# MCISO-S08-V00-HallDifferentials.net
KiCad netlist of a schematic drawn in Altium Designer
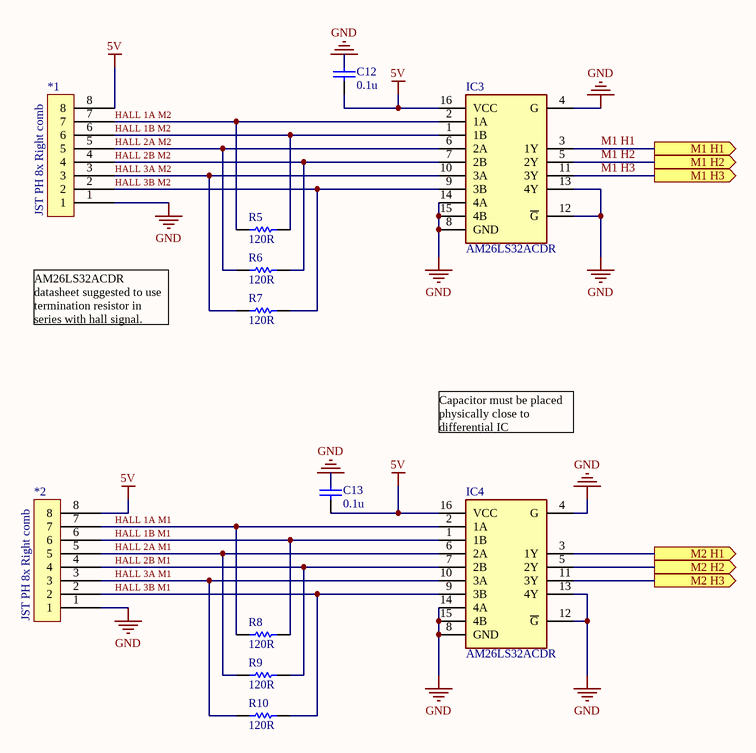
[diagram p0: MCISO-S08-V00-HallDifferentials.SchDoc]

(export (version "E")
  (design (tool "Eeschema 10.0.6"))
  (components
    (comp (ref "*1")
      (value "JST PH 8x Right comb")
      (footprint "JST PH 8x RIGHT SMD")
      (libsource (lib "QUTMS-MCISOLibrary") (part "JST PH 8x Right comb"))
    )
    (comp (ref "*2")
      (value "JST PH 8x Right comb")
      (footprint "JST PH 8x RIGHT SMD")
      (libsource (lib "QUTMS-MCISOLibrary") (part "JST PH 8x Right comb"))
    )
    (comp (ref "C12")
      (value "0.1u")
      (footprint "Cap_Ceramic_0603")
      (description "Capacitor, Ceramic, SMD, 4u7, 50V, 5%, X7R, 0603")
      (libsource (lib "QUTMS-MCISOLibrary") (part "4u7 50V 5% X7R 0603"))
    )
    (comp (ref "C13")
      (value "0.1u")
      (footprint "Cap_Ceramic_0603")
      (description "Capacitor, Ceramic, SMD, 4u7, 50V, 5%, X7R, 0603")
      (libsource (lib "QUTMS-MCISOLibrary") (part "4u7 50V 5% X7R 0603"))
    )
    (comp (ref "IC3")
      (value "AM26LS32ACDR")
      (footprint "SamacSys:SOIC127P600X175-16N")
      (description "Integrated Circuit")
      (fields (field (name "MOUSER PART NUMBER") "595-AM26LS32ACDR"))
      (libsource (lib "QUTMS-MCISOLibrary") (part "AM26LS32ACDR"))
    )
    (comp (ref "IC4")
      (value "AM26LS32ACDR")
      (footprint "SamacSys:SOIC127P600X175-16N")
      (description "Integrated Circuit")
      (fields (field (name "MOUSER PART NUMBER") "595-AM26LS32ACDR"))
      (libsource (lib "QUTMS-MCISOLibrary") (part "AM26LS32ACDR"))
    )
    (comp (ref "R5")
      (value "120R")
      (footprint "Res_ThinFilm_1210")
      (description "Resistor, SMD, 120R, 0.25W, 1%, 1210")
      (libsource (lib "QUTMS-MCISOLibrary") (part "120R 1% 1210"))
    )
    (comp (ref "R6")
      (value "120R")
      (footprint "Res_ThinFilm_1210")
      (description "Resistor, SMD, 120R, 0.25W, 1%, 1210")
      (libsource (lib "QUTMS-MCISOLibrary") (part "120R 1% 1210"))
    )
    (comp (ref "R7")
      (value "120R")
      (footprint "Res_ThinFilm_1210")
      (description "Resistor, SMD, 120R, 0.25W, 1%, 1210")
      (libsource (lib "QUTMS-MCISOLibrary") (part "120R 1% 1210"))
    )
    (comp (ref "R8")
      (value "120R")
      (footprint "Res_ThinFilm_1210")
      (description "Resistor, SMD, 120R, 0.25W, 1%, 1210")
      (libsource (lib "QUTMS-MCISOLibrary") (part "120R 1% 1210"))
    )
    (comp (ref "R9")
      (value "120R")
      (footprint "Res_ThinFilm_1210")
      (description "Resistor, SMD, 120R, 0.25W, 1%, 1210")
      (libsource (lib "QUTMS-MCISOLibrary") (part "120R 1% 1210"))
    )
    (comp (ref "R10")
      (value "120R")
      (footprint "Res_ThinFilm_1210")
      (description "Resistor, SMD, 120R, 0.25W, 1%, 1210")
      (libsource (lib "QUTMS-MCISOLibrary") (part "120R 1% 1210"))
    )
  )
  (nets
    (net (code "1") (name "/HALL 1A M1") (class "Default")
      (node (ref "*2") (pin "7") (pinfunction "7_7") (pintype "passive"))
      (node (ref "IC4") (pin "2") (pinfunction "1A_2") (pintype "passive"))
      (node (ref "R8") (pin "1") (pinfunction "1_1") (pintype "passive"))
    )
    (net (code "2") (name "/HALL 1A M2") (class "Default")
      (node (ref "*1") (pin "7") (pinfunction "7_7") (pintype "passive"))
      (node (ref "IC3") (pin "2") (pinfunction "1A_2") (pintype "passive"))
      (node (ref "R5") (pin "1") (pinfunction "1_1") (pintype "passive"))
    )
    (net (code "3") (name "/HALL 1B M1") (class "Default")
      (node (ref "*2") (pin "6") (pinfunction "6_6") (pintype "passive"))
      (node (ref "IC4") (pin "1") (pinfunction "1B_1") (pintype "passive"))
      (node (ref "R8") (pin "2") (pinfunction "2_2") (pintype "passive"))
    )
    (net (code "4") (name "/HALL 1B M2") (class "Default")
      (node (ref "*1") (pin "6") (pinfunction "6_6") (pintype "passive"))
      (node (ref "IC3") (pin "1") (pinfunction "1B_1") (pintype "passive"))
      (node (ref "R5") (pin "2") (pinfunction "2_2") (pintype "passive"))
    )
    (net (code "5") (name "/HALL 2A M1") (class "Default")
      (node (ref "*2") (pin "5") (pinfunction "5_5") (pintype "passive"))
      (node (ref "IC4") (pin "6") (pinfunction "2A_6") (pintype "passive"))
      (node (ref "R9") (pin "1") (pinfunction "1_1") (pintype "passive"))
    )
    (net (code "6") (name "/HALL 2A M2") (class "Default")
      (node (ref "*1") (pin "5") (pinfunction "5_5") (pintype "passive"))
      (node (ref "IC3") (pin "6") (pinfunction "2A_6") (pintype "passive"))
      (node (ref "R6") (pin "1") (pinfunction "1_1") (pintype "passive"))
    )
    (net (code "7") (name "/HALL 2B M1") (class "Default")
      (node (ref "*2") (pin "4") (pinfunction "4_4") (pintype "passive"))
      (node (ref "IC4") (pin "7") (pinfunction "2B_7") (pintype "passive"))
      (node (ref "R9") (pin "2") (pinfunction "2_2") (pintype "passive"))
    )
    (net (code "8") (name "/HALL 2B M2") (class "Default")
      (node (ref "*1") (pin "4") (pinfunction "4_4") (pintype "passive"))
      (node (ref "IC3") (pin "7") (pinfunction "2B_7") (pintype "passive"))
      (node (ref "R6") (pin "2") (pinfunction "2_2") (pintype "passive"))
    )
    (net (code "9") (name "/HALL 3A M1") (class "Default")
      (node (ref "*2") (pin "3") (pinfunction "3_3") (pintype "passive"))
      (node (ref "IC4") (pin "10") (pinfunction "3A_10") (pintype "passive"))
      (node (ref "R10") (pin "1") (pinfunction "1_1") (pintype "passive"))
    )
    (net (code "10") (name "/HALL 3A M2") (class "Default")
      (node (ref "*1") (pin "3") (pinfunction "3_3") (pintype "passive"))
      (node (ref "IC3") (pin "10") (pinfunction "3A_10") (pintype "passive"))
      (node (ref "R7") (pin "1") (pinfunction "1_1") (pintype "passive"))
    )
    (net (code "11") (name "/HALL 3B M1") (class "Default")
      (node (ref "*2") (pin "2") (pinfunction "2_2") (pintype "passive"))
      (node (ref "IC4") (pin "9") (pinfunction "3B_9") (pintype "passive"))
      (node (ref "R10") (pin "2") (pinfunction "2_2") (pintype "passive"))
    )
    (net (code "12") (name "/HALL 3B M2") (class "Default")
      (node (ref "*1") (pin "2") (pinfunction "2_2") (pintype "passive"))
      (node (ref "IC3") (pin "9") (pinfunction "3B_9") (pintype "passive"))
      (node (ref "R7") (pin "2") (pinfunction "2_2") (pintype "passive"))
    )
    (net (code "13") (name "/M1 H1") (class "Default")
      (node (ref "IC3") (pin "3") (pinfunction "1Y_3") (pintype "passive"))
    )
    (net (code "14") (name "/M1 H2") (class "Default")
      (node (ref "IC3") (pin "5") (pinfunction "2Y_5") (pintype "passive"))
    )
    (net (code "15") (name "/M1 H3") (class "Default")
      (node (ref "IC3") (pin "11") (pinfunction "3Y_11") (pintype "passive"))
    )
    (net (code "16") (name "/M2 H1") (class "Default")
      (node (ref "IC4") (pin "3") (pinfunction "1Y_3") (pintype "passive"))
    )
    (net (code "17") (name "/M2 H2") (class "Default")
      (node (ref "IC4") (pin "5") (pinfunction "2Y_5") (pintype "passive"))
    )
    (net (code "18") (name "/M2 H3") (class "Default")
      (node (ref "IC4") (pin "11") (pinfunction "3Y_11") (pintype "passive"))
    )
    (net (code "19") (name "5V") (class "Default")
      (node (ref "*1") (pin "8") (pinfunction "8_8") (pintype "passive"))
      (node (ref "*2") (pin "8") (pinfunction "8_8") (pintype "passive"))
      (node (ref "C12") (pin "2") (pinfunction "2_2") (pintype "passive"))
      (node (ref "C13") (pin "2") (pinfunction "2_2") (pintype "passive"))
      (node (ref "IC3") (pin "16") (pinfunction "VCC_16") (pintype "passive"))
      (node (ref "IC4") (pin "16") (pinfunction "VCC_16") (pintype "passive"))
    )
    (net (code "20") (name "GND") (class "Default")
      (node (ref "*1") (pin "1") (pinfunction "1_1") (pintype "passive"))
      (node (ref "*2") (pin "1") (pinfunction "1_1") (pintype "passive"))
      (node (ref "C12") (pin "1") (pinfunction "1_1") (pintype "passive"))
      (node (ref "C13") (pin "1") (pinfunction "1_1") (pintype "passive"))
      (node (ref "IC3") (pin "12") (pinfunction "~{G}_12") (pintype "passive"))
      (node (ref "IC3") (pin "13") (pinfunction "4Y_13") (pintype "passive"))
      (node (ref "IC3") (pin "14") (pinfunction "4A_14") (pintype "passive"))
      (node (ref "IC3") (pin "15") (pinfunction "4B_15") (pintype "passive"))
      (node (ref "IC3") (pin "4") (pinfunction "G_4") (pintype "passive"))
      (node (ref "IC3") (pin "8") (pinfunction "GND_8") (pintype "passive"))
      (node (ref "IC4") (pin "12") (pinfunction "~{G}_12") (pintype "passive"))
      (node (ref "IC4") (pin "13") (pinfunction "4Y_13") (pintype "passive"))
      (node (ref "IC4") (pin "14") (pinfunction "4A_14") (pintype "passive"))
      (node (ref "IC4") (pin "15") (pinfunction "4B_15") (pintype "passive"))
      (node (ref "IC4") (pin "4") (pinfunction "G_4") (pintype "passive"))
      (node (ref "IC4") (pin "8") (pinfunction "GND_8") (pintype "passive"))
    )
  )
)
